# Vertap_IMU.net
KiCad netlist of a schematic drawn in Altium Designer
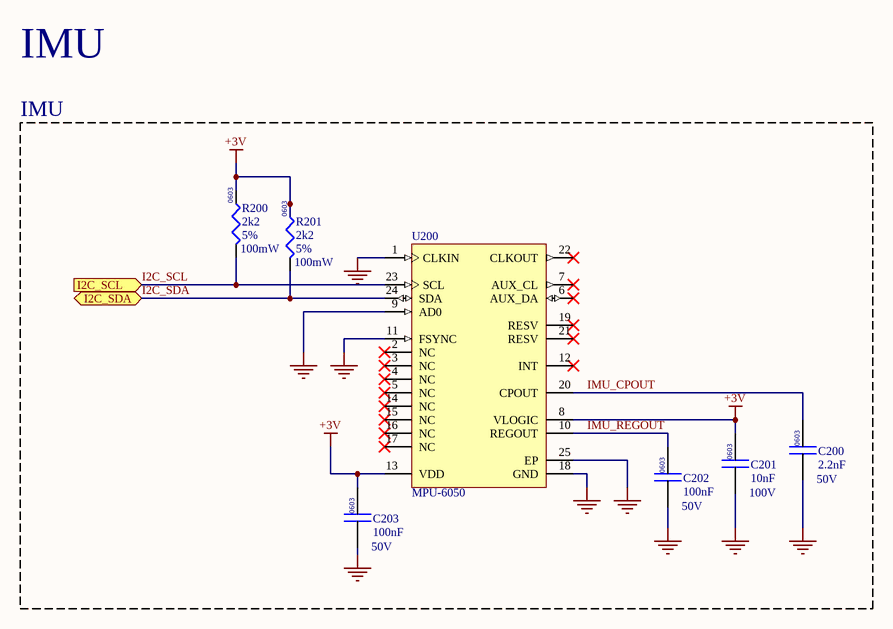
[diagram p0: Vertap_IMU.SchDoc]

(export (version "E")
  (design (tool "Eeschema 10.0.6"))
  (components
    (comp (ref "C200")
      (value "2.2nF")
      (footprint "CAP_0603_MURATA")
      (description "2200 pF ±20% 50V Ceramic Capacitor X7R 0603 (1608 Metric)")
      (libsource (lib "Vertap_SchLib") (part "CAP_2.2nF_0603"))
    )
    (comp (ref "C201")
      (value "10nF")
      (footprint "CAP_0603_MURATA")
      (description "CAP CER 10000PF 100V X7R 0603")
      (libsource (lib "Vertap_SchLib") (part "CAP_10nF_0603"))
    )
    (comp (ref "C202")
      (value "100nF")
      (footprint "CAP_0603_MURATA")
      (description "CAP CER 0.1UF 50V X7R 0603")
      (libsource (lib "Vertap_SchLib") (part "CAP_0.1uF_0603"))
    )
    (comp (ref "C203")
      (value "100nF")
      (footprint "CAP_0603_MURATA")
      (description "CAP CER 0.1UF 50V X7R 0603")
      (libsource (lib "Vertap_SchLib") (part "CAP_0.1uF_0603"))
    )
    (comp (ref "R200")
      (value "2k2")
      (footprint "RES_0603_YAGEO")
      (description "RES 2.2K OHM 5% 1/10W 0603")
      (fields
        (field (name "MANUFACTURER") "YAGEO")
        (field (name "MANUFACTURER PART NUMBER") "RC0603JR-072K2L")
      )
      (libsource (lib "Vertap_SchLib") (part "RES_0603_2.2K"))
    )
    (comp (ref "R201")
      (value "2k2")
      (footprint "RES_0603_YAGEO")
      (description "RES 2.2K OHM 5% 1/10W 0603")
      (fields
        (field (name "MANUFACTURER") "YAGEO")
        (field (name "MANUFACTURER PART NUMBER") "RC0603JR-072K2L")
      )
      (libsource (lib "Vertap_SchLib") (part "RES_0603_2.2K"))
    )
    (comp (ref "U200")
      (value "MPU-6050")
      (footprint "IS-QFN-24_V")
      (description "Analog Circuit, 1 Func, CMOS")
      (libsource (lib "taldabba") (part "IS-MPU-6050-QFN-24"))
    )
  )
  (nets
    (net (code "1") (name "+3V") (class "Default")
      (node (ref "C201") (pin "1") (pinfunction "1_1") (pintype "passive"))
      (node (ref "C203") (pin "1") (pinfunction "1_1") (pintype "passive"))
      (node (ref "R200") (pin "1") (pinfunction "1_1") (pintype "passive"))
      (node (ref "R201") (pin "1") (pinfunction "1_1") (pintype "passive"))
      (node (ref "U200") (pin "13") (pinfunction "VDD_13") (pintype "power_in"))
      (node (ref "U200") (pin "8") (pinfunction "VLOGIC_8") (pintype "power_in"))
    )
    (net (code "2") (name "/I2C_SCL") (class "Default")
      (node (ref "R200") (pin "2") (pinfunction "2_2") (pintype "passive"))
      (node (ref "U200") (pin "23") (pinfunction "SCL_23") (pintype "input"))
    )
    (net (code "3") (name "/I2C_SDA") (class "Default")
      (node (ref "R201") (pin "2") (pinfunction "2_2") (pintype "passive"))
      (node (ref "U200") (pin "24") (pinfunction "SDA_24") (pintype "bidirectional"))
    )
    (net (code "4") (name "/IMU_CPOUT") (class "Default")
      (node (ref "C200") (pin "1") (pinfunction "1_1") (pintype "passive"))
      (node (ref "U200") (pin "20") (pinfunction "CPOUT_20") (pintype "passive"))
    )
    (net (code "5") (name "/IMU_REGOUT") (class "Default")
      (node (ref "C202") (pin "1") (pinfunction "1_1") (pintype "passive"))
      (node (ref "U200") (pin "10") (pinfunction "REGOUT_10") (pintype "passive"))
    )
    (net (code "6") (name "GND") (class "Default")
      (node (ref "C200") (pin "2") (pinfunction "2_2") (pintype "passive"))
      (node (ref "C201") (pin "2") (pinfunction "2_2") (pintype "passive"))
      (node (ref "C202") (pin "2") (pinfunction "2_2") (pintype "passive"))
      (node (ref "C203") (pin "2") (pinfunction "2_2") (pintype "passive"))
      (node (ref "U200") (pin "1") (pinfunction "CLKIN_1") (pintype "input"))
      (node (ref "U200") (pin "11") (pinfunction "FSYNC_11") (pintype "input"))
      (node (ref "U200") (pin "18") (pinfunction "GND_18") (pintype "power_in"))
      (node (ref "U200") (pin "25") (pinfunction "EP_25") (pintype "power_in"))
      (node (ref "U200") (pin "9") (pinfunction "AD0_9") (pintype "input"))
    )
    (net (code "7") (name "unconnected-(U200-AUX_CL-Pad7)") (class "Default")
      (node (ref "U200") (pin "7") (pinfunction "AUX_CL_7") (pintype "output+no_connect"))
    )
    (net (code "8") (name "unconnected-(U200-AUX_DA-Pad6)") (class "Default")
      (node (ref "U200") (pin "6") (pinfunction "AUX_DA_6") (pintype "bidirectional+no_connect"))
    )
    (net (code "9") (name "unconnected-(U200-CLKOUT-Pad22)") (class "Default")
      (node (ref "U200") (pin "22") (pinfunction "CLKOUT_22") (pintype "output+no_connect"))
    )
    (net (code "10") (name "unconnected-(U200-INT-Pad12)") (class "Default")
      (node (ref "U200") (pin "12") (pinfunction "INT_12") (pintype "open_collector+no_connect"))
    )
    (net (code "11") (name "unconnected-(U200-NC-Pad2)") (class "Default")
      (node (ref "U200") (pin "2") (pinfunction "NC_2") (pintype "passive+no_connect"))
    )
    (net (code "12") (name "unconnected-(U200-NC-Pad3)") (class "Default")
      (node (ref "U200") (pin "3") (pinfunction "NC_3") (pintype "passive+no_connect"))
    )
    (net (code "13") (name "unconnected-(U200-NC-Pad4)") (class "Default")
      (node (ref "U200") (pin "4") (pinfunction "NC_4") (pintype "passive+no_connect"))
    )
    (net (code "14") (name "unconnected-(U200-NC-Pad5)") (class "Default")
      (node (ref "U200") (pin "5") (pinfunction "NC_5") (pintype "passive+no_connect"))
    )
    (net (code "15") (name "unconnected-(U200-NC-Pad14)") (class "Default")
      (node (ref "U200") (pin "14") (pinfunction "NC_14") (pintype "passive+no_connect"))
    )
    (net (code "16") (name "unconnected-(U200-NC-Pad15)") (class "Default")
      (node (ref "U200") (pin "15") (pinfunction "NC_15") (pintype "passive+no_connect"))
    )
    (net (code "17") (name "unconnected-(U200-NC-Pad16)") (class "Default")
      (node (ref "U200") (pin "16") (pinfunction "NC_16") (pintype "passive+no_connect"))
    )
    (net (code "18") (name "unconnected-(U200-NC-Pad17)") (class "Default")
      (node (ref "U200") (pin "17") (pinfunction "NC_17") (pintype "passive+no_connect"))
    )
    (net (code "19") (name "unconnected-(U200-RESV-Pad19)") (class "Default")
      (node (ref "U200") (pin "19") (pinfunction "RESV_19") (pintype "passive+no_connect"))
    )
    (net (code "20") (name "unconnected-(U200-RESV-Pad21)") (class "Default")
      (node (ref "U200") (pin "21") (pinfunction "RESV_21") (pintype "passive+no_connect"))
    )
  )
)
